# practice_2.net
KiCad netlist of a schematic drawn in EAGLE
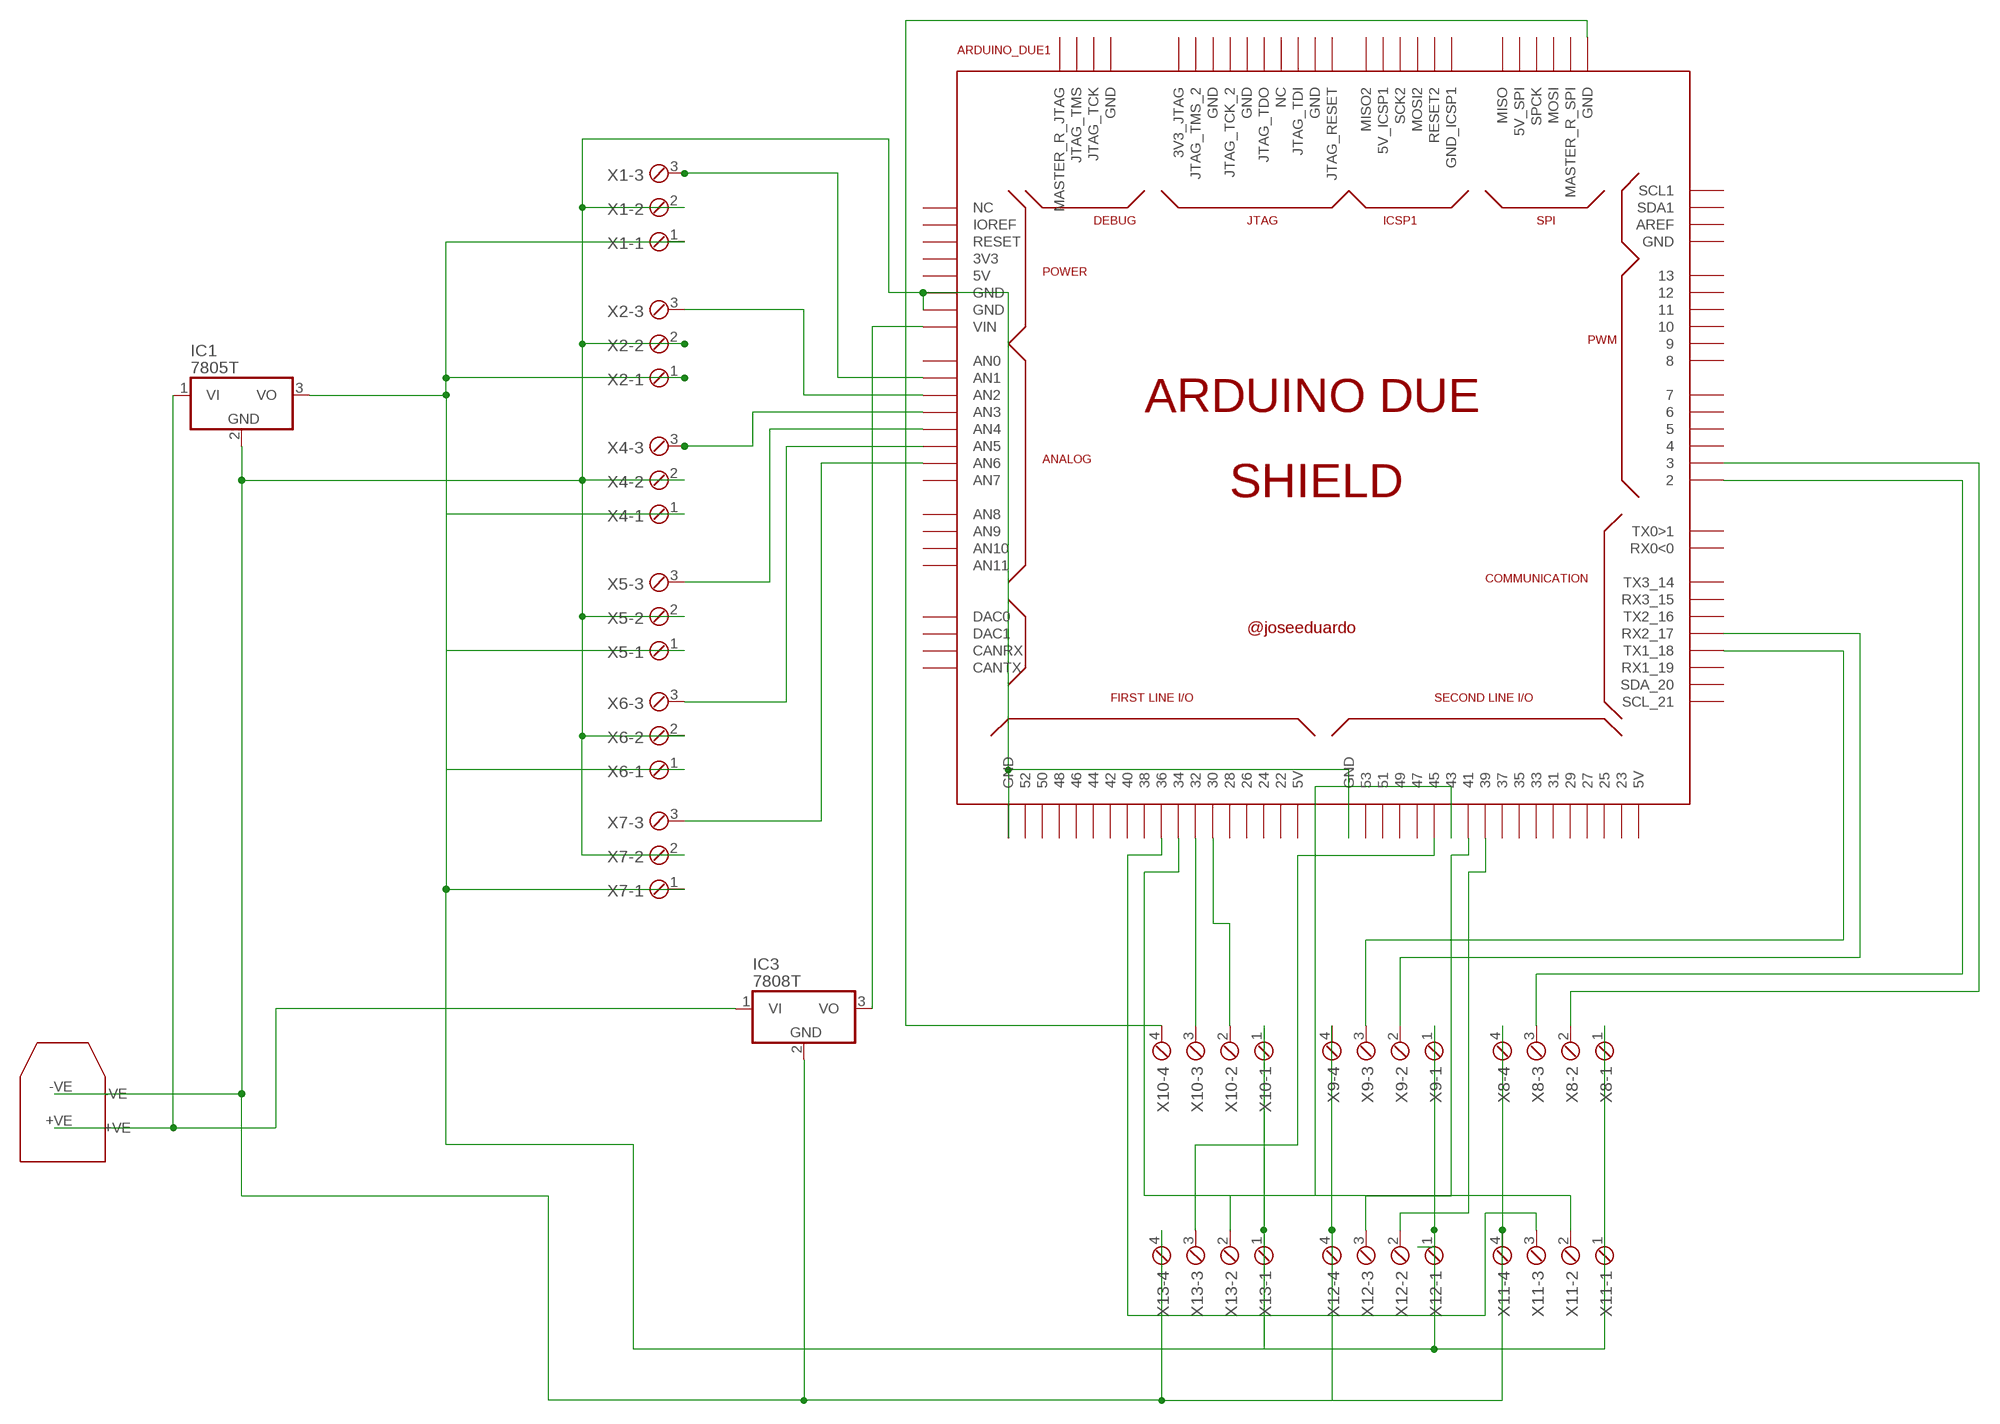
[diagram p0: schematic, sheet 1]

(export (version "E")
  (design (tool "Eeschema 10.0.6"))
  (components
    (comp (ref "ARDUINO_DUE1")
      (value "ARDUINO_DUE_SHIELD")
      (footprint "eagle-import:ARDUINO_DUE_SHIELD")
      (libsource (lib "eagle-import") (part "ARDUINO_DUE_SHIELD"))
    )
    (comp (ref "IC1")
      (value "7805T")
      (footprint "eagle-import:TO220H")
      (libsource (lib "eagle-import") (part "78T05"))
    )
    (comp (ref "IC3")
      (value "7808T")
      (footprint "eagle-import:TO220H")
      (libsource (lib "eagle-import") (part "78T08"))
    )
    (comp (ref "U$1")
      (value "XT60XT60")
      (footprint "eagle-import:XT60")
      (libsource (lib "eagle-import") (part "XT60XT60"))
    )
    (comp (ref "X1")
      (value "MPT3")
      (footprint "eagle-import:3POL254")
      (libsource (lib "eagle-import") (part "MPT3"))
    )
    (comp (ref "X2")
      (value "MPT3")
      (footprint "eagle-import:3POL254")
      (libsource (lib "eagle-import") (part "MPT3"))
    )
    (comp (ref "X4")
      (value "MPT3")
      (footprint "eagle-import:3POL254")
      (libsource (lib "eagle-import") (part "MPT3"))
    )
    (comp (ref "X5")
      (value "MPT3")
      (footprint "eagle-import:3POL254")
      (libsource (lib "eagle-import") (part "MPT3"))
    )
    (comp (ref "X6")
      (value "MPT3")
      (footprint "eagle-import:3POL254")
      (libsource (lib "eagle-import") (part "MPT3"))
    )
    (comp (ref "X7")
      (value "MPT3")
      (footprint "eagle-import:3POL254")
      (libsource (lib "eagle-import") (part "MPT3"))
    )
    (comp (ref "X8")
      (value "MPT4")
      (footprint "eagle-import:4POL254")
      (libsource (lib "eagle-import") (part "MPT4"))
    )
    (comp (ref "X9")
      (value "MPT4")
      (footprint "eagle-import:4POL254")
      (libsource (lib "eagle-import") (part "MPT4"))
    )
    (comp (ref "X10")
      (value "MPT4")
      (footprint "eagle-import:4POL254")
      (libsource (lib "eagle-import") (part "MPT4"))
    )
    (comp (ref "X11")
      (value "MPT4")
      (footprint "eagle-import:4POL254")
      (libsource (lib "eagle-import") (part "MPT4"))
    )
    (comp (ref "X12")
      (value "MPT4")
      (footprint "eagle-import:4POL254")
      (libsource (lib "eagle-import") (part "MPT4"))
    )
    (comp (ref "X13")
      (value "MPT4")
      (footprint "eagle-import:4POL254")
      (libsource (lib "eagle-import") (part "MPT4"))
    )
  )
  (nets
    (net (code "1") (name "Net-(ARDUINO_DUE1-AN1)") (class "Default")
      (node (ref "ARDUINO_DUE1") (pin "A1") (pinfunction "AN1_A1") (pintype "bidirectional"))
      (node (ref "X1") (pin "3") (pinfunction "1_3") (pintype "passive"))
    )
    (net (code "2") (name "Net-(ARDUINO_DUE1-AN2)") (class "Default")
      (node (ref "ARDUINO_DUE1") (pin "A2") (pinfunction "AN2_A2") (pintype "bidirectional"))
      (node (ref "X2") (pin "3") (pinfunction "1_3") (pintype "passive"))
    )
    (net (code "3") (name "Net-(ARDUINO_DUE1-AN3)") (class "Default")
      (node (ref "ARDUINO_DUE1") (pin "A3") (pinfunction "AN3_A3") (pintype "bidirectional"))
      (node (ref "X4") (pin "3") (pinfunction "1_3") (pintype "passive"))
    )
    (net (code "4") (name "Net-(ARDUINO_DUE1-AN4)") (class "Default")
      (node (ref "ARDUINO_DUE1") (pin "A4") (pinfunction "AN4_A4") (pintype "bidirectional"))
      (node (ref "X5") (pin "3") (pinfunction "1_3") (pintype "passive"))
    )
    (net (code "5") (name "Net-(ARDUINO_DUE1-AN5)") (class "Default")
      (node (ref "ARDUINO_DUE1") (pin "A5") (pinfunction "AN5_A5") (pintype "bidirectional"))
      (node (ref "X6") (pin "3") (pinfunction "1_3") (pintype "passive"))
    )
    (net (code "6") (name "Net-(ARDUINO_DUE1-AN6)") (class "Default")
      (node (ref "ARDUINO_DUE1") (pin "A6") (pinfunction "AN6_A6") (pintype "bidirectional"))
      (node (ref "X7") (pin "3") (pinfunction "1_3") (pintype "passive"))
    )
    (net (code "7") (name "Net-(ARDUINO_DUE1-RX2_17)") (class "Default")
      (node (ref "ARDUINO_DUE1") (pin "17") (pinfunction "RX2_17_17") (pintype "bidirectional"))
      (node (ref "X9") (pin "2") (pinfunction "1_2") (pintype "passive"))
    )
    (net (code "8") (name "Net-(ARDUINO_DUE1-TX1_18)") (class "Default")
      (node (ref "ARDUINO_DUE1") (pin "18") (pinfunction "TX1_18_18") (pintype "bidirectional"))
      (node (ref "X9") (pin "3") (pinfunction "1_3") (pintype "passive"))
    )
    (net (code "9") (name "Net-(IC1-GND)") (class "Default")
      (node (ref "ARDUINO_DUE1") (pin "GND") (pinfunction "GND_GND") (pintype "bidirectional"))
      (node (ref "ARDUINO_DUE1") (pin "GND_1") (pinfunction "GND_GND_1") (pintype "bidirectional"))
      (node (ref "ARDUINO_DUE1") (pin "GND_2") (pinfunction "GND_GND_2") (pintype "bidirectional"))
      (node (ref "ARDUINO_DUE1") (pin "GND_3") (pinfunction "GND_GND_3") (pintype "bidirectional"))
      (node (ref "IC1") (pin "2") (pinfunction "GND_2") (pintype "passive"))
      (node (ref "IC3") (pin "2") (pinfunction "GND_2") (pintype "passive"))
      (node (ref "U$1") (pin "-VE") (pinfunction "-VE_-VE") (pintype "bidirectional"))
      (node (ref "X1") (pin "2") (pinfunction "1_2") (pintype "passive"))
      (node (ref "X11") (pin "4") (pinfunction "1_4") (pintype "passive"))
      (node (ref "X12") (pin "4") (pinfunction "1_4") (pintype "passive"))
      (node (ref "X13") (pin "4") (pinfunction "1_4") (pintype "passive"))
      (node (ref "X2") (pin "2") (pinfunction "1_2") (pintype "passive"))
      (node (ref "X4") (pin "2") (pinfunction "1_2") (pintype "passive"))
      (node (ref "X5") (pin "2") (pinfunction "1_2") (pintype "passive"))
      (node (ref "X6") (pin "2") (pinfunction "1_2") (pintype "passive"))
      (node (ref "X7") (pin "2") (pinfunction "1_2") (pintype "passive"))
      (node (ref "X8") (pin "4") (pinfunction "1_4") (pintype "passive"))
      (node (ref "X9") (pin "4") (pinfunction "1_4") (pintype "passive"))
    )
    (net (code "10") (name "Net-(IC1-VI)") (class "Default")
      (node (ref "IC1") (pin "1") (pinfunction "VI_1") (pintype "input"))
      (node (ref "IC3") (pin "1") (pinfunction "VI_1") (pintype "input"))
      (node (ref "U$1") (pin "+VE") (pinfunction "+VE_+VE") (pintype "bidirectional"))
    )
    (net (code "11") (name "Net-(IC1-VO)") (class "Default")
      (node (ref "IC1") (pin "3") (pinfunction "VO_3") (pintype "passive"))
      (node (ref "X1") (pin "1") (pinfunction "1_1") (pintype "passive"))
      (node (ref "X10") (pin "1") (pinfunction "1_1") (pintype "passive"))
      (node (ref "X11") (pin "1") (pinfunction "1_1") (pintype "passive"))
      (node (ref "X12") (pin "1") (pinfunction "1_1") (pintype "passive"))
      (node (ref "X13") (pin "1") (pinfunction "1_1") (pintype "passive"))
      (node (ref "X2") (pin "1") (pinfunction "1_1") (pintype "passive"))
      (node (ref "X4") (pin "1") (pinfunction "1_1") (pintype "passive"))
      (node (ref "X5") (pin "1") (pinfunction "1_1") (pintype "passive"))
      (node (ref "X6") (pin "1") (pinfunction "1_1") (pintype "passive"))
      (node (ref "X7") (pin "1") (pinfunction "1_1") (pintype "passive"))
      (node (ref "X8") (pin "1") (pinfunction "1_1") (pintype "passive"))
      (node (ref "X9") (pin "1") (pinfunction "1_1") (pintype "passive"))
    )
    (net (code "12") (name "Net-(IC3-VO)") (class "Default")
      (node (ref "ARDUINO_DUE1") (pin "VIN") (pinfunction "VIN_VIN") (pintype "bidirectional"))
      (node (ref "IC3") (pin "3") (pinfunction "VO_3") (pintype "passive"))
    )
    (net (code "13") (name "Net-(X8B-1)") (class "Default")
      (node (ref "ARDUINO_DUE1") (pin "3") (pinfunction "3_3") (pintype "bidirectional"))
      (node (ref "X8") (pin "2") (pinfunction "1_2") (pintype "passive"))
    )
    (net (code "14") (name "Net-(X8C-1)") (class "Default")
      (node (ref "ARDUINO_DUE1") (pin "2") (pinfunction "2_2") (pintype "bidirectional"))
      (node (ref "X8") (pin "3") (pinfunction "1_3") (pintype "passive"))
    )
    (net (code "15") (name "Net-(X10B-1)") (class "Default")
      (node (ref "ARDUINO_DUE1") (pin "30") (pinfunction "30_30") (pintype "bidirectional"))
      (node (ref "X10") (pin "2") (pinfunction "1_2") (pintype "passive"))
    )
    (net (code "16") (name "Net-(X10C-1)") (class "Default")
      (node (ref "ARDUINO_DUE1") (pin "32") (pinfunction "32_32") (pintype "bidirectional"))
      (node (ref "X10") (pin "3") (pinfunction "1_3") (pintype "passive"))
    )
    (net (code "17") (name "Net-(X10D-1)") (class "Default")
      (node (ref "ARDUINO_DUE1") (pin "GND_5") (pinfunction "GND_GND_5") (pintype "bidirectional"))
      (node (ref "X10") (pin "4") (pinfunction "1_4") (pintype "passive"))
    )
    (net (code "18") (name "Net-(X11B-1)") (class "Default")
      (node (ref "ARDUINO_DUE1") (pin "34") (pinfunction "34_34") (pintype "bidirectional"))
      (node (ref "X11") (pin "2") (pinfunction "1_2") (pintype "passive"))
    )
    (net (code "19") (name "Net-(X11C-1)") (class "Default")
      (node (ref "ARDUINO_DUE1") (pin "36") (pinfunction "36_36") (pintype "bidirectional"))
      (node (ref "X11") (pin "3") (pinfunction "1_3") (pintype "passive"))
    )
    (net (code "20") (name "Net-(X12B-1)") (class "Default")
      (node (ref "ARDUINO_DUE1") (pin "39") (pinfunction "39_39") (pintype "bidirectional"))
      (node (ref "X12") (pin "2") (pinfunction "1_2") (pintype "passive"))
    )
    (net (code "21") (name "Net-(X12C-1)") (class "Default")
      (node (ref "ARDUINO_DUE1") (pin "41") (pinfunction "41_41") (pintype "bidirectional"))
      (node (ref "X12") (pin "3") (pinfunction "1_3") (pintype "passive"))
    )
    (net (code "22") (name "Net-(X13B-1)") (class "Default")
      (node (ref "ARDUINO_DUE1") (pin "43") (pinfunction "43_43") (pintype "bidirectional"))
      (node (ref "X13") (pin "2") (pinfunction "1_2") (pintype "passive"))
    )
    (net (code "23") (name "Net-(X13C-1)") (class "Default")
      (node (ref "ARDUINO_DUE1") (pin "45") (pinfunction "45_45") (pintype "bidirectional"))
      (node (ref "X13") (pin "3") (pinfunction "1_3") (pintype "passive"))
    )
    (net (code "24") (name "unconnected-(ARDUINO_DUE1-5V-Pad5V0)") (class "Default")
      (node (ref "ARDUINO_DUE1") (pin "5V0") (pinfunction "5V_5V0") (pintype "bidirectional"))
    )
    (net (code "25") (name "unconnected-(ARDUINO_DUE1-5V-Pad5V0_1)") (class "Default")
      (node (ref "ARDUINO_DUE1") (pin "5V0_1") (pinfunction "5V_5V0_1") (pintype "bidirectional"))
    )
    (net (code "26") (name "unconnected-(ARDUINO_DUE1-5V-Pad5V0_2)") (class "Default")
      (node (ref "ARDUINO_DUE1") (pin "5V0_2") (pinfunction "5V_5V0_2") (pintype "bidirectional"))
    )
    (net (code "27") (name "unconnected-(ARDUINO_DUE1-5V_SPI-Pad5V_2)") (class "Default")
      (node (ref "ARDUINO_DUE1") (pin "5V_2") (pinfunction "5V_SPI_5V_2") (pintype "bidirectional"))
    )
    (net (code "28") (name "unconnected-(ARDUINO_DUE1-AN0-PadA0)") (class "Default")
      (node (ref "ARDUINO_DUE1") (pin "A0") (pinfunction "AN0_A0") (pintype "bidirectional"))
    )
    (net (code "29") (name "unconnected-(ARDUINO_DUE1-AN7-PadA7)") (class "Default")
      (node (ref "ARDUINO_DUE1") (pin "A7") (pinfunction "AN7_A7") (pintype "bidirectional"))
    )
    (net (code "30") (name "unconnected-(ARDUINO_DUE1-AN8-PadA8)") (class "Default")
      (node (ref "ARDUINO_DUE1") (pin "A8") (pinfunction "AN8_A8") (pintype "bidirectional"))
    )
    (net (code "31") (name "unconnected-(ARDUINO_DUE1-AN9-PadA9)") (class "Default")
      (node (ref "ARDUINO_DUE1") (pin "A9") (pinfunction "AN9_A9") (pintype "bidirectional"))
    )
    (net (code "32") (name "unconnected-(ARDUINO_DUE1-AN10-PadA10)") (class "Default")
      (node (ref "ARDUINO_DUE1") (pin "A10") (pinfunction "AN10_A10") (pintype "bidirectional"))
    )
    (net (code "33") (name "unconnected-(ARDUINO_DUE1-AN11-PadA11)") (class "Default")
      (node (ref "ARDUINO_DUE1") (pin "A11") (pinfunction "AN11_A11") (pintype "bidirectional"))
    )
    (net (code "34") (name "unconnected-(ARDUINO_DUE1-GND-PadGND_4)") (class "Default")
      (node (ref "ARDUINO_DUE1") (pin "GND_4") (pinfunction "GND_GND_4") (pintype "bidirectional"))
    )
    (net (code "35") (name "unconnected-(ARDUINO_DUE1-GND-PadGND_7)") (class "Default")
      (node (ref "ARDUINO_DUE1") (pin "GND_7") (pinfunction "GND_GND_7") (pintype "bidirectional"))
    )
    (net (code "36") (name "unconnected-(ARDUINO_DUE1-GND-PadGND_8)") (class "Default")
      (node (ref "ARDUINO_DUE1") (pin "GND_8") (pinfunction "GND_GND_8") (pintype "bidirectional"))
    )
    (net (code "37") (name "unconnected-(ARDUINO_DUE1-GND-PadGND_9)") (class "Default")
      (node (ref "ARDUINO_DUE1") (pin "GND_9") (pinfunction "GND_GND_9") (pintype "bidirectional"))
    )
    (net (code "38") (name "unconnected-(ARDUINO_DUE1-GND-PadGND_10)") (class "Default")
      (node (ref "ARDUINO_DUE1") (pin "GND_10") (pinfunction "GND_GND_10") (pintype "bidirectional"))
    )
    (net (code "39") (name "unconnected-(ARDUINO_DUE1-MASTER_R_JTAG-PadMASTER_RESET_JTAG)") (class "Default")
      (node (ref "ARDUINO_DUE1") (pin "MASTER_RESET_JTAG") (pinfunction "MASTER_R_JTAG_MASTER_RESET_JTAG") (pintype "bidirectional"))
    )
    (net (code "40") (name "unconnected-(ARDUINO_DUE1-MASTER_R_SPI-PadMASTER_RESET_SPI)") (class "Default")
      (node (ref "ARDUINO_DUE1") (pin "MASTER_RESET_SPI") (pinfunction "MASTER_R_SPI_MASTER_RESET_SPI") (pintype "bidirectional"))
    )
    (net (code "41") (name "unconnected-(ARDUINO_DUE1-NC-PadNC_2)") (class "Default")
      (node (ref "ARDUINO_DUE1") (pin "NC_2") (pinfunction "NC_NC_2") (pintype "no_connect"))
    )
    (net (code "42") (name "unconnected-(ARDUINO_DUE1-NC-PadNC_5)") (class "Default")
      (node (ref "ARDUINO_DUE1") (pin "NC_5") (pinfunction "NC_NC_5") (pintype "bidirectional"))
    )
    (net (code "43") (name "unconnected-(ARDUINO_DUE1-Pad3V3)") (class "Default")
      (node (ref "ARDUINO_DUE1") (pin "3V3") (pinfunction "3V3_3V3") (pintype "bidirectional"))
    )
    (net (code "44") (name "unconnected-(ARDUINO_DUE1-Pad3V3_JTAG)") (class "Default")
      (node (ref "ARDUINO_DUE1") (pin "3V3_JTAG") (pinfunction "3V3_JTAG_3V3_JTAG") (pintype "bidirectional"))
    )
    (net (code "45") (name "unconnected-(ARDUINO_DUE1-Pad4)") (class "Default")
      (node (ref "ARDUINO_DUE1") (pin "4") (pinfunction "4_4") (pintype "bidirectional"))
    )
    (net (code "46") (name "unconnected-(ARDUINO_DUE1-Pad5)") (class "Default")
      (node (ref "ARDUINO_DUE1") (pin "5") (pinfunction "5_5") (pintype "bidirectional"))
    )
    (net (code "47") (name "unconnected-(ARDUINO_DUE1-Pad5V_ICSP1)") (class "Default")
      (node (ref "ARDUINO_DUE1") (pin "5V_ICSP1") (pinfunction "5V_ICSP1_5V_ICSP1") (pintype "bidirectional"))
    )
    (net (code "48") (name "unconnected-(ARDUINO_DUE1-Pad6)") (class "Default")
      (node (ref "ARDUINO_DUE1") (pin "6") (pinfunction "6_6") (pintype "bidirectional"))
    )
    (net (code "49") (name "unconnected-(ARDUINO_DUE1-Pad7)") (class "Default")
      (node (ref "ARDUINO_DUE1") (pin "7") (pinfunction "7_7") (pintype "bidirectional"))
    )
    (net (code "50") (name "unconnected-(ARDUINO_DUE1-Pad8)") (class "Default")
      (node (ref "ARDUINO_DUE1") (pin "8") (pinfunction "8_8") (pintype "bidirectional"))
    )
    (net (code "51") (name "unconnected-(ARDUINO_DUE1-Pad9)") (class "Default")
      (node (ref "ARDUINO_DUE1") (pin "9") (pinfunction "9_9") (pintype "bidirectional"))
    )
    (net (code "52") (name "unconnected-(ARDUINO_DUE1-Pad10)") (class "Default")
      (node (ref "ARDUINO_DUE1") (pin "10") (pinfunction "10_10") (pintype "bidirectional"))
    )
    (net (code "53") (name "unconnected-(ARDUINO_DUE1-Pad11)") (class "Default")
      (node (ref "ARDUINO_DUE1") (pin "11") (pinfunction "11_11") (pintype "bidirectional"))
    )
    (net (code "54") (name "unconnected-(ARDUINO_DUE1-Pad12)") (class "Default")
      (node (ref "ARDUINO_DUE1") (pin "12") (pinfunction "12_12") (pintype "bidirectional"))
    )
    (net (code "55") (name "unconnected-(ARDUINO_DUE1-Pad13)") (class "Default")
      (node (ref "ARDUINO_DUE1") (pin "13") (pinfunction "13_13") (pintype "bidirectional"))
    )
    (net (code "56") (name "unconnected-(ARDUINO_DUE1-Pad22)") (class "Default")
      (node (ref "ARDUINO_DUE1") (pin "22") (pinfunction "22_22") (pintype "bidirectional"))
    )
    (net (code "57") (name "unconnected-(ARDUINO_DUE1-Pad23)") (class "Default")
      (node (ref "ARDUINO_DUE1") (pin "23") (pinfunction "23_23") (pintype "bidirectional"))
    )
    (net (code "58") (name "unconnected-(ARDUINO_DUE1-Pad24)") (class "Default")
      (node (ref "ARDUINO_DUE1") (pin "24") (pinfunction "24_24") (pintype "bidirectional"))
    )
    (net (code "59") (name "unconnected-(ARDUINO_DUE1-Pad25)") (class "Default")
      (node (ref "ARDUINO_DUE1") (pin "25") (pinfunction "25_25") (pintype "bidirectional"))
    )
    (net (code "60") (name "unconnected-(ARDUINO_DUE1-Pad26)") (class "Default")
      (node (ref "ARDUINO_DUE1") (pin "26") (pinfunction "26_26") (pintype "bidirectional"))
    )
    (net (code "61") (name "unconnected-(ARDUINO_DUE1-Pad27)") (class "Default")
      (node (ref "ARDUINO_DUE1") (pin "27") (pinfunction "27_27") (pintype "bidirectional"))
    )
    (net (code "62") (name "unconnected-(ARDUINO_DUE1-Pad28)") (class "Default")
      (node (ref "ARDUINO_DUE1") (pin "28") (pinfunction "28_28") (pintype "bidirectional"))
    )
    (net (code "63") (name "unconnected-(ARDUINO_DUE1-Pad29)") (class "Default")
      (node (ref "ARDUINO_DUE1") (pin "29") (pinfunction "29_29") (pintype "bidirectional"))
    )
    (net (code "64") (name "unconnected-(ARDUINO_DUE1-Pad31)") (class "Default")
      (node (ref "ARDUINO_DUE1") (pin "31") (pinfunction "31_31") (pintype "bidirectional"))
    )
    (net (code "65") (name "unconnected-(ARDUINO_DUE1-Pad33)") (class "Default")
      (node (ref "ARDUINO_DUE1") (pin "33") (pinfunction "33_33") (pintype "bidirectional"))
    )
    (net (code "66") (name "unconnected-(ARDUINO_DUE1-Pad35)") (class "Default")
      (node (ref "ARDUINO_DUE1") (pin "35") (pinfunction "35_35") (pintype "bidirectional"))
    )
    (net (code "67") (name "unconnected-(ARDUINO_DUE1-Pad37)") (class "Default")
      (node (ref "ARDUINO_DUE1") (pin "37") (pinfunction "37_37") (pintype "bidirectional"))
    )
    (net (code "68") (name "unconnected-(ARDUINO_DUE1-Pad38)") (class "Default")
      (node (ref "ARDUINO_DUE1") (pin "38") (pinfunction "38_38") (pintype "bidirectional"))
    )
    (net (code "69") (name "unconnected-(ARDUINO_DUE1-Pad40)") (class "Default")
      (node (ref "ARDUINO_DUE1") (pin "40") (pinfunction "40_40") (pintype "bidirectional"))
    )
    (net (code "70") (name "unconnected-(ARDUINO_DUE1-Pad42)") (class "Default")
      (node (ref "ARDUINO_DUE1") (pin "42") (pinfunction "42_42") (pintype "bidirectional"))
    )
    (net (code "71") (name "unconnected-(ARDUINO_DUE1-Pad44)") (class "Default")
      (node (ref "ARDUINO_DUE1") (pin "44") (pinfunction "44_44") (pintype "bidirectional"))
    )
    (net (code "72") (name "unconnected-(ARDUINO_DUE1-Pad46)") (class "Default")
      (node (ref "ARDUINO_DUE1") (pin "46") (pinfunction "46_46") (pintype "bidirectional"))
    )
    (net (code "73") (name "unconnected-(ARDUINO_DUE1-Pad47)") (class "Default")
      (node (ref "ARDUINO_DUE1") (pin "47") (pinfunction "47_47") (pintype "bidirectional"))
    )
    (net (code "74") (name "unconnected-(ARDUINO_DUE1-Pad48)") (class "Default")
      (node (ref "ARDUINO_DUE1") (pin "48") (pinfunction "48_48") (pintype "bidirectional"))
    )
    (net (code "75") (name "unconnected-(ARDUINO_DUE1-Pad49)") (class "Default")
      (node (ref "ARDUINO_DUE1") (pin "49") (pinfunction "49_49") (pintype "bidirectional"))
    )
    (net (code "76") (name "unconnected-(ARDUINO_DUE1-Pad50)") (class "Default")
      (node (ref "ARDUINO_DUE1") (pin "50") (pinfunction "50_50") (pintype "bidirectional"))
    )
    (net (code "77") (name "unconnected-(ARDUINO_DUE1-Pad51)") (class "Default")
      (node (ref "ARDUINO_DUE1") (pin "51") (pinfunction "51_51") (pintype "bidirectional"))
    )
    (net (code "78") (name "unconnected-(ARDUINO_DUE1-Pad52)") (class "Default")
      (node (ref "ARDUINO_DUE1") (pin "52") (pinfunction "52_52") (pintype "bidirectional"))
    )
    (net (code "79") (name "unconnected-(ARDUINO_DUE1-Pad53)") (class "Default")
      (node (ref "ARDUINO_DUE1") (pin "53") (pinfunction "53_53") (pintype "bidirectional"))
    )
    (net (code "80") (name "unconnected-(ARDUINO_DUE1-PadAREF)") (class "Default")
      (node (ref "ARDUINO_DUE1") (pin "AREF") (pinfunction "AREF_AREF") (pintype "bidirectional"))
    )
    (net (code "81") (name "unconnected-(ARDUINO_DUE1-PadCANRX)") (class "Default")
      (node (ref "ARDUINO_DUE1") (pin "CANRX") (pinfunction "CANRX_CANRX") (pintype "bidirectional"))
    )
    (net (code "82") (name "unconnected-(ARDUINO_DUE1-PadCANTX)") (class "Default")
      (node (ref "ARDUINO_DUE1") (pin "CANTX") (pinfunction "CANTX_CANTX") (pintype "bidirectional"))
    )
    (net (code "83") (name "unconnected-(ARDUINO_DUE1-PadDAC0)") (class "Default")
      (node (ref "ARDUINO_DUE1") (pin "DAC0") (pinfunction "DAC0_DAC0") (pintype "bidirectional"))
    )
    (net (code "84") (name "unconnected-(ARDUINO_DUE1-PadDAC1)") (class "Default")
      (node (ref "ARDUINO_DUE1") (pin "DAC1") (pinfunction "DAC1_DAC1") (pintype "bidirectional"))
    )
    (net (code "85") (name "unconnected-(ARDUINO_DUE1-PadGND_ICSP1)") (class "Default")
      (node (ref "ARDUINO_DUE1") (pin "GND_ICSP1") (pinfunction "GND_ICSP1_GND_ICSP1") (pintype "bidirectional"))
    )
    (net (code "86") (name "unconnected-(ARDUINO_DUE1-PadIOREF)") (class "Default")
      (node (ref "ARDUINO_DUE1") (pin "IOREF") (pinfunction "IOREF_IOREF") (pintype "bidirectional"))
    )
    (net (code "87") (name "unconnected-(ARDUINO_DUE1-PadJTAG_RESET)") (class "Default")
      (node (ref "ARDUINO_DUE1") (pin "JTAG_RESET") (pinfunction "JTAG_RESET_JTAG_RESET") (pintype "bidirectional"))
    )
    (net (code "88") (name "unconnected-(ARDUINO_DUE1-PadJTAG_TCK)") (class "Default")
      (node (ref "ARDUINO_DUE1") (pin "JTAG_TCK") (pinfunction "JTAG_TCK_JTAG_TCK") (pintype "bidirectional"))
    )
    (net (code "89") (name "unconnected-(ARDUINO_DUE1-PadJTAG_TCK_2)") (class "Default")
      (node (ref "ARDUINO_DUE1") (pin "JTAG_TCK_2") (pinfunction "JTAG_TCK_2_JTAG_TCK_2") (pintype "bidirectional"))
    )
    (net (code "90") (name "unconnected-(ARDUINO_DUE1-PadJTAG_TDI)") (class "Default")
      (node (ref "ARDUINO_DUE1") (pin "JTAG_TDI") (pinfunction "JTAG_TDI_JTAG_TDI") (pintype "bidirectional"))
    )
    (net (code "91") (name "unconnected-(ARDUINO_DUE1-PadJTAG_TDO)") (class "Default")
      (node (ref "ARDUINO_DUE1") (pin "JTAG_TDO") (pinfunction "JTAG_TDO_JTAG_TDO") (pintype "bidirectional"))
    )
    (net (code "92") (name "unconnected-(ARDUINO_DUE1-PadJTAG_TMS)") (class "Default")
      (node (ref "ARDUINO_DUE1") (pin "JTAG_TMS") (pinfunction "JTAG_TMS_JTAG_TMS") (pintype "bidirectional"))
    )
    (net (code "93") (name "unconnected-(ARDUINO_DUE1-PadJTAG_TMS_2)") (class "Default")
      (node (ref "ARDUINO_DUE1") (pin "JTAG_TMS_2") (pinfunction "JTAG_TMS_2_JTAG_TMS_2") (pintype "bidirectional"))
    )
    (net (code "94") (name "unconnected-(ARDUINO_DUE1-PadMISO)") (class "Default")
      (node (ref "ARDUINO_DUE1") (pin "MISO") (pinfunction "MISO_MISO") (pintype "bidirectional"))
    )
    (net (code "95") (name "unconnected-(ARDUINO_DUE1-PadMISO2)") (class "Default")
      (node (ref "ARDUINO_DUE1") (pin "MISO2") (pinfunction "MISO2_MISO2") (pintype "bidirectional"))
    )
    (net (code "96") (name "unconnected-(ARDUINO_DUE1-PadMOSI)") (class "Default")
      (node (ref "ARDUINO_DUE1") (pin "MOSI") (pinfunction "MOSI_MOSI") (pintype "bidirectional"))
    )
    (net (code "97") (name "unconnected-(ARDUINO_DUE1-PadMOSI2)") (class "Default")
      (node (ref "ARDUINO_DUE1") (pin "MOSI2") (pinfunction "MOSI2_MOSI2") (pintype "bidirectional"))
    )
    (net (code "98") (name "unconnected-(ARDUINO_DUE1-PadRESET)") (class "Default")
      (node (ref "ARDUINO_DUE1") (pin "RESET") (pinfunction "RESET_RESET") (pintype "bidirectional"))
    )
    (net (code "99") (name "unconnected-(ARDUINO_DUE1-PadRESET2)") (class "Default")
      (node (ref "ARDUINO_DUE1") (pin "RESET2") (pinfunction "RESET2_RESET2") (pintype "bidirectional"))
    )
    (net (code "100") (name "unconnected-(ARDUINO_DUE1-PadSCK2)") (class "Default")
      (node (ref "ARDUINO_DUE1") (pin "SCK2") (pinfunction "SCK2_SCK2") (pintype "bidirectional"))
    )
    (net (code "101") (name "unconnected-(ARDUINO_DUE1-PadSCL1)") (class "Default")
      (node (ref "ARDUINO_DUE1") (pin "SCL1") (pinfunction "SCL1_SCL1") (pintype "bidirectional"))
    )
    (net (code "102") (name "unconnected-(ARDUINO_DUE1-PadSDA1)") (class "Default")
      (node (ref "ARDUINO_DUE1") (pin "SDA1") (pinfunction "SDA1_SDA1") (pintype "bidirectional"))
    )
    (net (code "103") (name "unconnected-(ARDUINO_DUE1-PadSPCK)") (class "Default")
      (node (ref "ARDUINO_DUE1") (pin "SPCK") (pinfunction "SPCK_SPCK") (pintype "bidirectional"))
    )
    (net (code "104") (name "unconnected-(ARDUINO_DUE1-RX0<0-Pad0)") (class "Default")
      (node (ref "ARDUINO_DUE1") (pin "0") (pinfunction "RX0<0_0") (pintype "bidirectional"))
    )
    (net (code "105") (name "unconnected-(ARDUINO_DUE1-RX1_19-Pad19)") (class "Default")
      (node (ref "ARDUINO_DUE1") (pin "19") (pinfunction "RX1_19_19") (pintype "bidirectional"))
    )
    (net (code "106") (name "unconnected-(ARDUINO_DUE1-RX3_15-Pad15)") (class "Default")
      (node (ref "ARDUINO_DUE1") (pin "15") (pinfunction "RX3_15_15") (pintype "bidirectional"))
    )
    (net (code "107") (name "unconnected-(ARDUINO_DUE1-SCL_21-Pad21)") (class "Default")
      (node (ref "ARDUINO_DUE1") (pin "21") (pinfunction "SCL_21_21") (pintype "bidirectional"))
    )
    (net (code "108") (name "unconnected-(ARDUINO_DUE1-SDA_20-Pad20)") (class "Default")
      (node (ref "ARDUINO_DUE1") (pin "20") (pinfunction "SDA_20_20") (pintype "bidirectional"))
    )
    (net (code "109") (name "unconnected-(ARDUINO_DUE1-TX0>1-Pad1)") (class "Default")
      (node (ref "ARDUINO_DUE1") (pin "1") (pinfunction "TX0>1_1") (pintype "bidirectional"))
    )
    (net (code "110") (name "unconnected-(ARDUINO_DUE1-TX2_16-Pad16)") (class "Default")
      (node (ref "ARDUINO_DUE1") (pin "16") (pinfunction "TX2_16_16") (pintype "bidirectional"))
    )
    (net (code "111") (name "unconnected-(ARDUINO_DUE1-TX3_14-Pad14)") (class "Default")
      (node (ref "ARDUINO_DUE1") (pin "14") (pinfunction "TX3_14_14") (pintype "bidirectional"))
    )
  )
)
